# Schematic.net
KiCad netlist of a schematic drawn in EAGLE
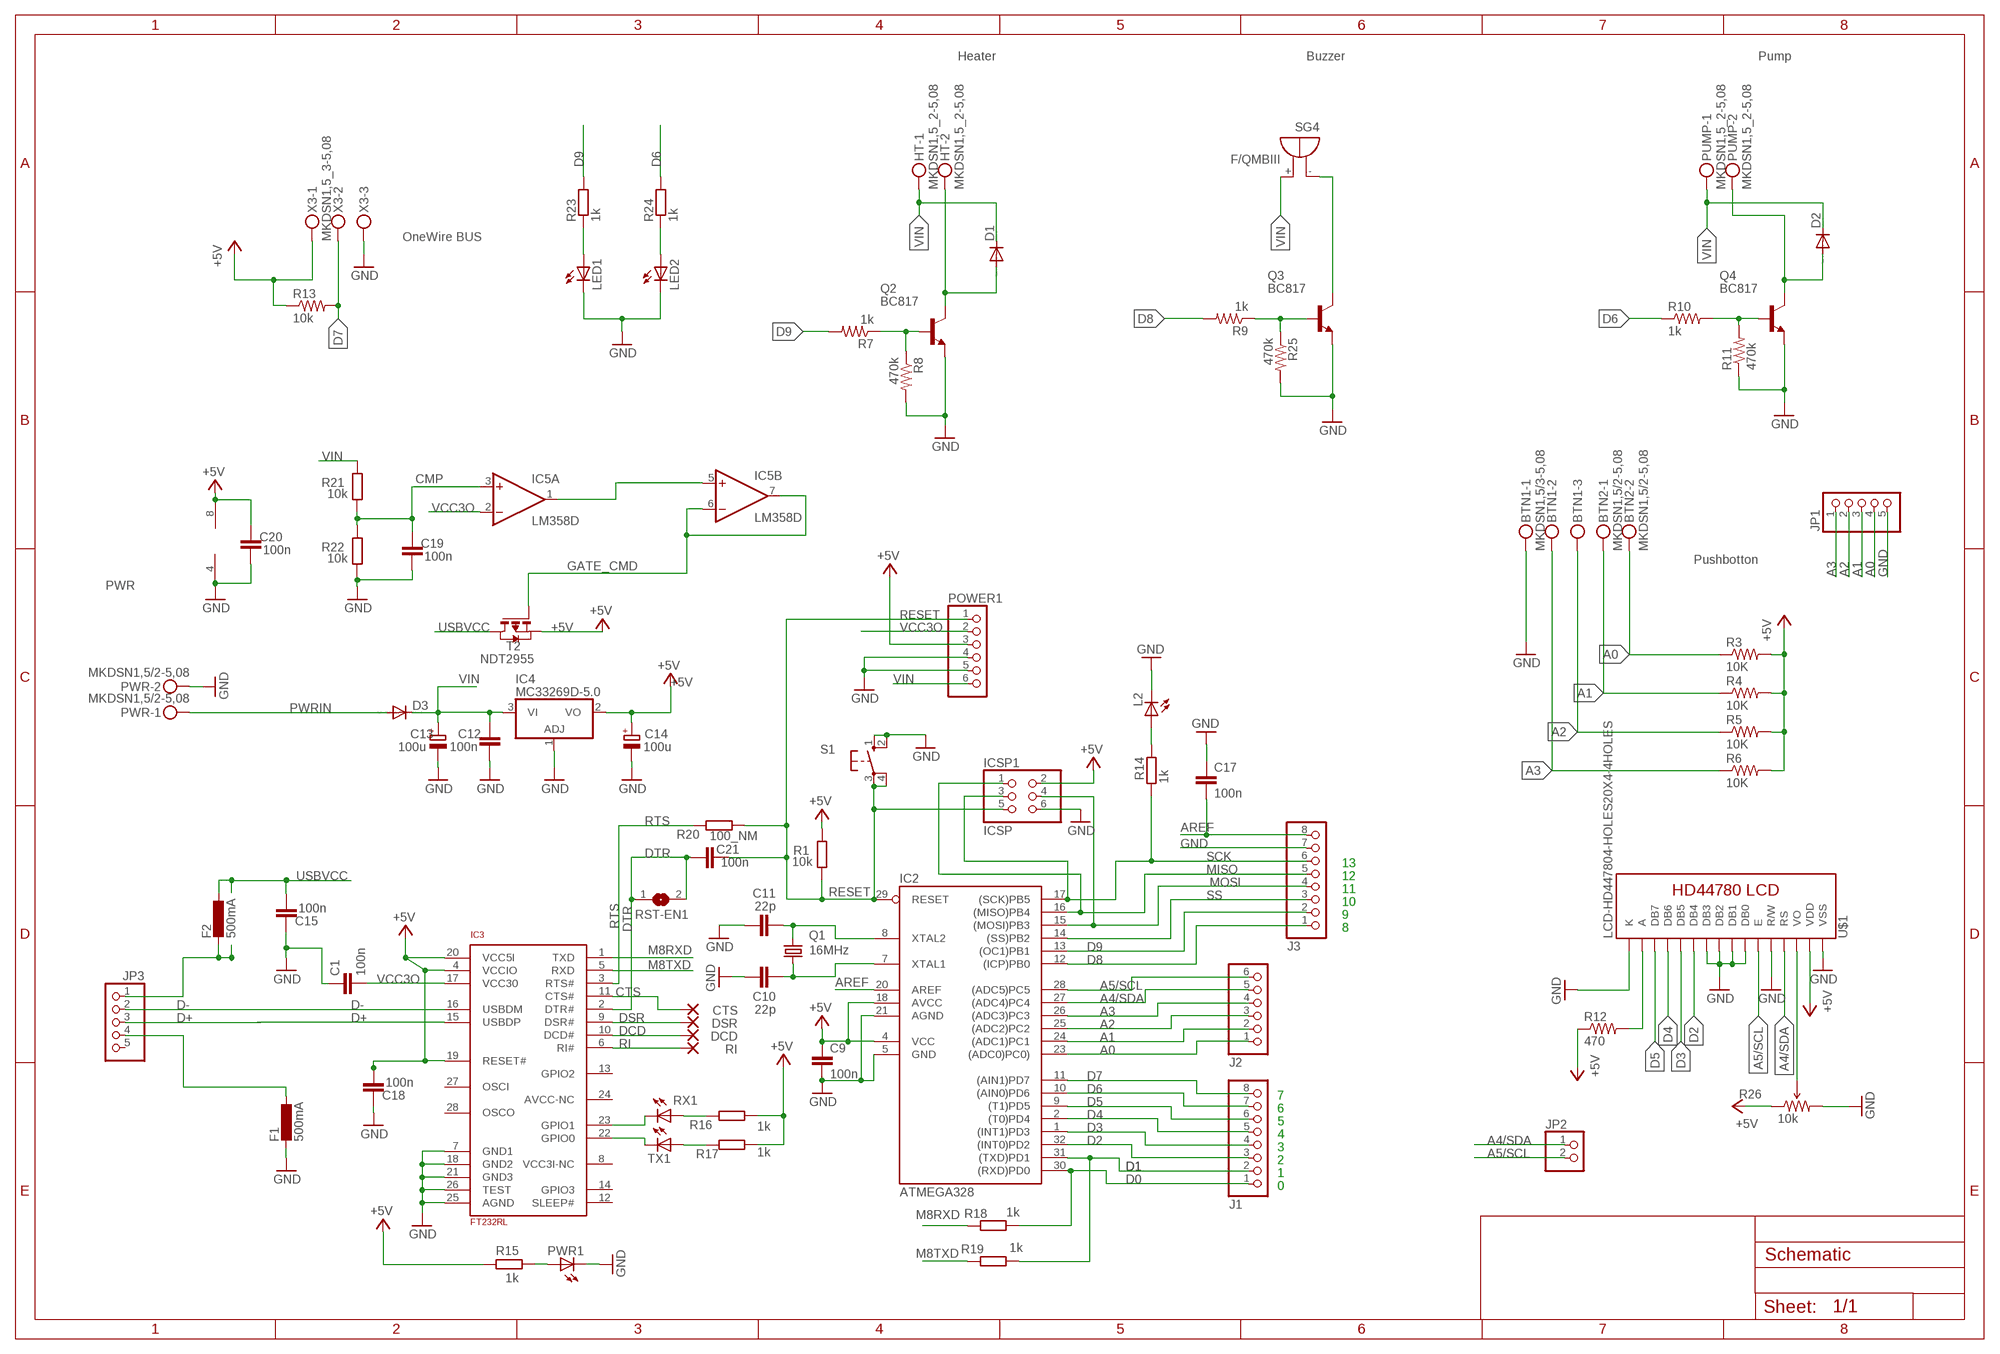
[diagram p0: schematic, sheet 1]

(export (version "E")
  (design (tool "Eeschema 10.0.6"))
  (components
    (comp (ref "BTN1")
      (value "MKDSN1,5/3-5,08")
      (footprint "eagle-import:MKDSN1,5_3-5,08")
      (fields (field (name "OC_NEWARK") "unknown"))
      (libsource (lib "eagle-import") (part "MKDSN1,5/3-5,08"))
    )
    (comp (ref "BTN2")
      (value "MKDSN1,5/2-5,08")
      (footprint "eagle-import:MKDSN1,5_2-5,08")
      (fields (field (name "OC_NEWARK") "unknown"))
      (libsource (lib "eagle-import") (part "MKDSN1,5/2-5,08"))
    )
    (comp (ref "C1")
      (value "100n")
      (footprint "eagle-import:C0603")
      (libsource (lib "eagle-import") (part "C-EUC0603"))
    )
    (comp (ref "C9")
      (value "100n")
      (footprint "eagle-import:C0603")
      (libsource (lib "eagle-import") (part "C-EUC0603"))
    )
    (comp (ref "C10")
      (value "22p")
      (footprint "eagle-import:C0603")
      (libsource (lib "eagle-import") (part "C-EUC0603"))
    )
    (comp (ref "C11")
      (value "22p")
      (footprint "eagle-import:C0603")
      (libsource (lib "eagle-import") (part "C-EUC0603"))
    )
    (comp (ref "C12")
      (value "100n")
      (footprint "eagle-import:C0603")
      (libsource (lib "eagle-import") (part "C-EUC0603"))
    )
    (comp (ref "C13")
      (value "100u")
      (footprint "eagle-import:PANASONIC_D")
      (libsource (lib "eagle-import") (part "CPOL-EUD"))
    )
    (comp (ref "C14")
      (value "100u")
      (footprint "eagle-import:PANASONIC_D")
      (libsource (lib "eagle-import") (part "CPOL-EUD"))
    )
    (comp (ref "C15")
      (value "100n")
      (footprint "eagle-import:C0603")
      (libsource (lib "eagle-import") (part "C-EUC0603"))
    )
    (comp (ref "C17")
      (value "100n")
      (footprint "eagle-import:C0603")
      (libsource (lib "eagle-import") (part "C-EUC0603"))
    )
    (comp (ref "C18")
      (value "100n")
      (footprint "eagle-import:C0603")
      (libsource (lib "eagle-import") (part "C-EUC0603"))
    )
    (comp (ref "C19")
      (value "100n")
      (footprint "eagle-import:C0603")
      (libsource (lib "eagle-import") (part "C-EUC0603"))
    )
    (comp (ref "C20")
      (value "100n")
      (footprint "eagle-import:C0603")
      (libsource (lib "eagle-import") (part "C-EUC0603"))
    )
    (comp (ref "C21")
      (value "100n")
      (footprint "eagle-import:C0603")
      (libsource (lib "eagle-import") (part "C-EUC0603"))
    )
    (comp (ref "CTS")
      (value "SMD2")
      (footprint "eagle-import:SMD1,27-2,54")
      (libsource (lib "eagle-import") (part "SMD2"))
    )
    (comp (ref "D1")
      (value "DIODE-SMB")
      (footprint "eagle-import:SMB")
      (libsource (lib "eagle-import") (part "DIODE-SMB"))
    )
    (comp (ref "D2")
      (value "DIODE-SMB")
      (footprint "eagle-import:SMB")
      (libsource (lib "eagle-import") (part "DIODE-SMB"))
    )
    (comp (ref "D3")
      (value "DIODE-SMB")
      (footprint "eagle-import:SMB")
      (libsource (lib "eagle-import") (part "DIODE-SMB"))
    )
    (comp (ref "DCD")
      (value "SMD2")
      (footprint "eagle-import:SMD1,27-2,54")
      (libsource (lib "eagle-import") (part "SMD2"))
    )
    (comp (ref "DSR")
      (value "SMD2")
      (footprint "eagle-import:SMD1,27-2,54")
      (libsource (lib "eagle-import") (part "SMD2"))
    )
    (comp (ref "F1")
      (value "500mA")
      (footprint "eagle-import:L1812")
      (libsource (lib "eagle-import") (part "L-EUL1812"))
    )
    (comp (ref "F2")
      (value "500mA")
      (footprint "eagle-import:L1812")
      (libsource (lib "eagle-import") (part "L-EUL1812"))
    )
    (comp (ref "HT")
      (value "MKDSN1,5_2-5,08")
      (footprint "eagle-import:MKDSN1,5-2-5,08")
      (fields (field (name "OC_NEWARK") "unknown"))
      (libsource (lib "eagle-import") (part "MKDSN1,5_2-5,08"))
    )
    (comp (ref "IC2")
      (value "ATMEGA328")
      (footprint "eagle-import:TQFP32-08")
      (libsource (lib "eagle-import") (part "AT90S4433A"))
    )
    (comp (ref "IC3")
      (value "FT232RL")
      (footprint "eagle-import:SSOP28")
      (libsource (lib "eagle-import") (part "FT232RL"))
    )
    (comp (ref "IC4")
      (value "MC33269D-5.0")
      (footprint "eagle-import:DPACK")
      (libsource (lib "eagle-import") (part "MC33269?D-5.0"))
    )
    (comp (ref "IC5")
      (value "LM358D")
      (footprint "eagle-import:SO08")
      (libsource (lib "eagle-import") (part "LM358D"))
    )
    (comp (ref "ICSP1")
      (value "ICSP")
      (footprint "eagle-import:2X03")
      (libsource (lib "eagle-import") (part "PINHD-2X3"))
    )
    (comp (ref "J1")
      (value "PINHD-1X8")
      (footprint "eagle-import:1X08")
      (libsource (lib "eagle-import") (part "PINHD-1X8"))
    )
    (comp (ref "J2")
      (value "PINHD-1X6")
      (footprint "eagle-import:1X06")
      (libsource (lib "eagle-import") (part "PINHD-1X6"))
    )
    (comp (ref "J3")
      (value "PINHD-1X8")
      (footprint "eagle-import:1X08")
      (libsource (lib "eagle-import") (part "PINHD-1X8"))
    )
    (comp (ref "JP1")
      (value "PINHD-1X5/90")
      (footprint "eagle-import:1X05_90")
      (libsource (lib "eagle-import") (part "PINHD-1X5/90"))
    )
    (comp (ref "JP2")
      (value "PINHD-1X2/90")
      (footprint "eagle-import:1X02_90")
      (libsource (lib "eagle-import") (part "PINHD-1X2/90"))
    )
    (comp (ref "JP3")
      (value "PINHD-1X5/90")
      (footprint "eagle-import:1X05_90")
      (libsource (lib "eagle-import") (part "PINHD-1X5/90"))
    )
    (comp (ref "L2")
      (value "LEDSML0805")
      (footprint "eagle-import:SML0805")
      (libsource (lib "eagle-import") (part "LEDSML0805"))
    )
    (comp (ref "LED1")
      (value "LED5MM")
      (footprint "eagle-import:LED5MM")
      (libsource (lib "eagle-import") (part "LED5MM"))
    )
    (comp (ref "LED2")
      (value "LED5MM")
      (footprint "eagle-import:LED5MM")
      (libsource (lib "eagle-import") (part "LED5MM"))
    )
    (comp (ref "POWER1")
      (value "PINHD-1X6")
      (footprint "eagle-import:1X06")
      (libsource (lib "eagle-import") (part "PINHD-1X6"))
    )
    (comp (ref "PUMP")
      (value "MKDSN1,5_2-5,08")
      (footprint "eagle-import:MKDSN1,5-2-5,08")
      (fields (field (name "OC_NEWARK") "unknown"))
      (libsource (lib "eagle-import") (part "MKDSN1,5_2-5,08"))
    )
    (comp (ref "PWR")
      (value "MKDSN1,5/2-5,08")
      (footprint "eagle-import:MKDSN1,5_2-5,08")
      (fields (field (name "OC_NEWARK") "unknown"))
      (libsource (lib "eagle-import") (part "MKDSN1,5/2-5,08"))
    )
    (comp (ref "PWR1")
      (value "LEDSML0805")
      (footprint "eagle-import:SML0805")
      (libsource (lib "eagle-import") (part "LEDSML0805"))
    )
    (comp (ref "Q1")
      (value "16MHz")
      (footprint "eagle-import:HC49_S")
      (libsource (lib "eagle-import") (part "CRYTALHC49S"))
    )
    (comp (ref "Q2")
      (value "BC817")
      (footprint "eagle-import:SOT23-BEC")
      (libsource (lib "eagle-import") (part "-NPN-SOT23-BECBC817"))
    )
    (comp (ref "Q3")
      (value "BC817")
      (footprint "eagle-import:SOT23-BEC")
      (libsource (lib "eagle-import") (part "-NPN-SOT23-BECBC817"))
    )
    (comp (ref "Q4")
      (value "BC817")
      (footprint "eagle-import:SOT23-BEC")
      (libsource (lib "eagle-import") (part "-NPN-SOT23-BECBC817"))
    )
    (comp (ref "R1")
      (value "10k")
      (footprint "eagle-import:R0603")
      (libsource (lib "eagle-import") (part "R-EU_R0603"))
    )
    (comp (ref "R3")
      (value "10K")
      (footprint "eagle-import:R0603")
      (libsource (lib "eagle-import") (part "R-US_R0603"))
    )
    (comp (ref "R4")
      (value "10K")
      (footprint "eagle-import:R0603")
      (libsource (lib "eagle-import") (part "R-US_R0603"))
    )
    (comp (ref "R5")
      (value "10K")
      (footprint "eagle-import:R0603")
      (libsource (lib "eagle-import") (part "R-US_R0603"))
    )
    (comp (ref "R6")
      (value "10K")
      (footprint "eagle-import:R0603")
      (libsource (lib "eagle-import") (part "R-US_R0603"))
    )
    (comp (ref "R7")
      (value "1k")
      (footprint "eagle-import:R0603")
      (libsource (lib "eagle-import") (part "R-US_R0603"))
    )
    (comp (ref "R8")
      (value "470k")
      (footprint "eagle-import:R0603")
      (libsource (lib "eagle-import") (part "R-US_R0603"))
    )
    (comp (ref "R9")
      (value "1k")
      (footprint "eagle-import:R0603")
      (libsource (lib "eagle-import") (part "R-US_R0603"))
    )
    (comp (ref "R10")
      (value "1k")
      (footprint "eagle-import:R0603")
      (libsource (lib "eagle-import") (part "R-US_R0603"))
    )
    (comp (ref "R11")
      (value "470k")
      (footprint "eagle-import:R0603")
      (libsource (lib "eagle-import") (part "R-US_R0603"))
    )
    (comp (ref "R12")
      (value "470")
      (footprint "eagle-import:R1206")
      (libsource (lib "eagle-import") (part "R-US_R1206"))
    )
    (comp (ref "R13")
      (value "10k")
      (footprint "eagle-import:R0603")
      (libsource (lib "eagle-import") (part "R-US_R0603"))
    )
    (comp (ref "R14")
      (value "1k")
      (footprint "eagle-import:R0603")
      (libsource (lib "eagle-import") (part "R-EU_R0603"))
    )
    (comp (ref "R15")
      (value "1k")
      (footprint "eagle-import:R0603")
      (libsource (lib "eagle-import") (part "R-EU_R0603"))
    )
    (comp (ref "R16")
      (value "1k")
      (footprint "eagle-import:R0603")
      (libsource (lib "eagle-import") (part "R-EU_R0603"))
    )
    (comp (ref "R17")
      (value "1k")
      (footprint "eagle-import:R0603")
      (libsource (lib "eagle-import") (part "R-EU_R0603"))
    )
    (comp (ref "R18")
      (value "1k")
      (footprint "eagle-import:R0603")
      (libsource (lib "eagle-import") (part "R-EU_R0603"))
    )
    (comp (ref "R19")
      (value "1k")
      (footprint "eagle-import:R0603")
      (libsource (lib "eagle-import") (part "R-EU_R0603"))
    )
    (comp (ref "R20")
      (value "100_NM")
      (footprint "eagle-import:R0603")
      (libsource (lib "eagle-import") (part "R-EU_R0603"))
    )
    (comp (ref "R21")
      (value "10k")
      (footprint "eagle-import:R0603")
      (libsource (lib "eagle-import") (part "R-EU_R0603"))
    )
    (comp (ref "R22")
      (value "10k")
      (footprint "eagle-import:R0603")
      (libsource (lib "eagle-import") (part "R-EU_R0603"))
    )
    (comp (ref "R23")
      (value "1k")
      (footprint "eagle-import:R0603")
      (libsource (lib "eagle-import") (part "R-EU_R0603"))
    )
    (comp (ref "R24")
      (value "1k")
      (footprint "eagle-import:R0603")
      (libsource (lib "eagle-import") (part "R-EU_R0603"))
    )
    (comp (ref "R25")
      (value "470k")
      (footprint "eagle-import:R0603")
      (libsource (lib "eagle-import") (part "R-US_R0603"))
    )
    (comp (ref "R26")
      (value "10k")
      (footprint "eagle-import:TRIMPOT-5MM")
      (libsource (lib "eagle-import") (part "TRIMPOTTRIMPOT-5MM"))
    )
    (comp (ref "RI")
      (value "SMD2")
      (footprint "eagle-import:SMD1,27-2,54")
      (libsource (lib "eagle-import") (part "SMD2"))
    )
    (comp (ref "RST-EN1")
      (value "SJ")
      (footprint "eagle-import:SJ")
      (libsource (lib "eagle-import") (part "SJ"))
    )
    (comp (ref "RX1")
      (value "LEDSML0805")
      (footprint "eagle-import:SML0805")
      (libsource (lib "eagle-import") (part "LEDSML0805"))
    )
    (comp (ref "S1")
      (value "10-XX")
      (footprint "eagle-import:B3F-10XX")
      (fields (field (name "MPN") "B3F-1000"))
      (libsource (lib "eagle-import") (part "10-XX"))
    )
    (comp (ref "SG4")
      (value "F/QMBIII")
      (footprint "eagle-import:F_QMBIII")
      (libsource (lib "eagle-import") (part "F/QMBIII"))
    )
    (comp (ref "T2")
      (value "NDT2955")
      (footprint "eagle-import:SOT223")
      (libsource (lib "eagle-import") (part "PMOSSOT223"))
    )
    (comp (ref "TX1")
      (value "LEDSML0805")
      (footprint "eagle-import:SML0805")
      (libsource (lib "eagle-import") (part "LEDSML0805"))
    )
    (comp (ref "U$1")
      (value "LCD-HD447804-HOLES20X4-4HOLES")
      (footprint "eagle-import:LCD-20X4-4HOLES")
      (libsource (lib "eagle-import") (part "LCD-HD4478020X4-4HOLES4-HOLES"))
    )
    (comp (ref "X3")
      (value "MKDSN1,5_3-5,08")
      (footprint "eagle-import:MKDSN1,5-3-5,08")
      (fields (field (name "OC_NEWARK") "unknown"))
      (libsource (lib "eagle-import") (part "MKDSN1,5_3-5,08"))
    )
  )
  (nets
    (net (code "1") (name "+5V") (class "Default")
      (node (ref "C14") (pin "+") (pinfunction "+_+") (pintype "passive"))
      (node (ref "C18") (pin "1") (pinfunction "1_1") (pintype "passive"))
      (node (ref "C20") (pin "2") (pinfunction "2_2") (pintype "passive"))
      (node (ref "C9") (pin "1") (pinfunction "1_1") (pintype "passive"))
      (node (ref "IC2") (pin "18") (pinfunction "AVCC_18") (pintype "power_in"))
      (node (ref "IC2") (pin "4") (pinfunction "VCC_4") (pintype "power_in"))
      (node (ref "IC3") (pin "19") (pinfunction "RESET#_19") (pintype "input"))
      (node (ref "IC3") (pin "20") (pinfunction "VCC5I_20") (pintype "power_in"))
      (node (ref "IC3") (pin "4") (pinfunction "VCCIO_4") (pintype "power_in"))
      (node (ref "IC4") (pin "2") (pinfunction "VO_2") (pintype "passive"))
      (node (ref "IC5") (pin "8") (pinfunction "V+_8") (pintype "power_in"))
      (node (ref "ICSP1") (pin "2") (pinfunction "2_2") (pintype "passive"))
      (node (ref "POWER1") (pin "3") (pinfunction "3_3") (pintype "passive"))
      (node (ref "R1") (pin "2") (pinfunction "2_2") (pintype "passive"))
      (node (ref "R12") (pin "1") (pinfunction "1_1") (pintype "passive"))
      (node (ref "R13") (pin "1") (pinfunction "1_1") (pintype "passive"))
      (node (ref "R15") (pin "1") (pinfunction "1_1") (pintype "passive"))
      (node (ref "R16") (pin "2") (pinfunction "2_2") (pintype "passive"))
      (node (ref "R17") (pin "2") (pinfunction "2_2") (pintype "passive"))
      (node (ref "R26") (pin "A") (pinfunction "CCW_A") (pintype "passive"))
      (node (ref "R3") (pin "2") (pinfunction "2_2") (pintype "passive"))
      (node (ref "R4") (pin "2") (pinfunction "2_2") (pintype "passive"))
      (node (ref "R5") (pin "2") (pinfunction "2_2") (pintype "passive"))
      (node (ref "R6") (pin "2") (pinfunction "2_2") (pintype "passive"))
      (node (ref "T2") (pin "3") (pinfunction "S_3") (pintype "passive"))
      (node (ref "U$1") (pin "P$2") (pinfunction "VDD_P$2") (pintype "power_in"))
      (node (ref "X3") (pin "1") (pinfunction "KL_1") (pintype "passive"))
    )
    (net (code "2") (name "/AREF") (class "Default")
      (node (ref "C17") (pin "2") (pinfunction "2_2") (pintype "passive"))
      (node (ref "IC2") (pin "20") (pinfunction "AREF_20") (pintype "passive"))
      (node (ref "J3") (pin "8") (pinfunction "8_8") (pintype "passive"))
    )
    (net (code "3") (name "/CMP") (class "Default")
      (node (ref "C19") (pin "2") (pinfunction "2_2") (pintype "passive"))
      (node (ref "IC5") (pin "3") (pinfunction "+IN_3") (pintype "input"))
      (node (ref "R21") (pin "1") (pinfunction "1_1") (pintype "passive"))
      (node (ref "R22") (pin "2") (pinfunction "2_2") (pintype "passive"))
    )
    (net (code "4") (name "/CTS") (class "Default")
      (node (ref "CTS") (pin "1") (pinfunction "P_1") (pintype "passive"))
      (node (ref "IC3") (pin "11") (pinfunction "CTS#_11") (pintype "input"))
    )
    (net (code "5") (name "/D+") (class "Default")
      (node (ref "IC3") (pin "15") (pinfunction "USBDP_15") (pintype "bidirectional"))
      (node (ref "JP3") (pin "3") (pinfunction "3_3") (pintype "passive"))
    )
    (net (code "6") (name "/D-") (class "Default")
      (node (ref "IC3") (pin "16") (pinfunction "USBDM_16") (pintype "bidirectional"))
      (node (ref "JP3") (pin "2") (pinfunction "2_2") (pintype "passive"))
    )
    (net (code "7") (name "/D0") (class "Default")
      (node (ref "IC2") (pin "30") (pinfunction "(RXD)PD0_30") (pintype "bidirectional"))
      (node (ref "J1") (pin "1") (pinfunction "1_1") (pintype "passive"))
      (node (ref "R18") (pin "1") (pinfunction "1_1") (pintype "passive"))
    )
    (net (code "8") (name "/D1") (class "Default")
      (node (ref "IC2") (pin "31") (pinfunction "(TXD)PD1_31") (pintype "bidirectional"))
      (node (ref "J1") (pin "2") (pinfunction "2_2") (pintype "passive"))
      (node (ref "R19") (pin "1") (pinfunction "1_1") (pintype "passive"))
    )
    (net (code "9") (name "/DCD") (class "Default")
      (node (ref "DCD") (pin "1") (pinfunction "P_1") (pintype "passive"))
      (node (ref "IC3") (pin "10") (pinfunction "DCD#_10") (pintype "input"))
    )
    (net (code "10") (name "/DSR") (class "Default")
      (node (ref "DSR") (pin "1") (pinfunction "P_1") (pintype "passive"))
      (node (ref "IC3") (pin "9") (pinfunction "DSR#_9") (pintype "input"))
    )
    (net (code "11") (name "/DTR") (class "Default")
      (node (ref "C21") (pin "1") (pinfunction "1_1") (pintype "passive"))
      (node (ref "IC3") (pin "2") (pinfunction "DTR#_2") (pintype "output"))
      (node (ref "RST-EN1") (pin "1") (pinfunction "1_1") (pintype "passive"))
      (node (ref "RST-EN1") (pin "2") (pinfunction "2_2") (pintype "passive"))
    )
    (net (code "12") (name "/GATE_CMD") (class "Default")
      (node (ref "IC5") (pin "6") (pinfunction "-IN_6") (pintype "input"))
      (node (ref "IC5") (pin "7") (pinfunction "OUT_7") (pintype "output"))
      (node (ref "T2") (pin "1") (pinfunction "G_1") (pintype "passive"))
    )
    (net (code "13") (name "/M8RXD") (class "Default")
      (node (ref "IC3") (pin "1") (pinfunction "TXD_1") (pintype "output"))
      (node (ref "R18") (pin "2") (pinfunction "2_2") (pintype "passive"))
    )
    (net (code "14") (name "/M8TXD") (class "Default")
      (node (ref "IC3") (pin "5") (pinfunction "RXD_5") (pintype "input"))
      (node (ref "R19") (pin "2") (pinfunction "2_2") (pintype "passive"))
    )
    (net (code "15") (name "/MISO") (class "Default")
      (node (ref "IC2") (pin "16") (pinfunction "(MISO)PB4_16") (pintype "bidirectional"))
      (node (ref "ICSP1") (pin "1") (pinfunction "1_1") (pintype "passive"))
      (node (ref "J3") (pin "5") (pinfunction "5_5") (pintype "passive"))
    )
    (net (code "16") (name "/MOSI") (class "Default")
      (node (ref "IC2") (pin "15") (pinfunction "(MOSI)PB3_15") (pintype "bidirectional"))
      (node (ref "ICSP1") (pin "4") (pinfunction "4_4") (pintype "passive"))
      (node (ref "J3") (pin "4") (pinfunction "4_4") (pintype "passive"))
    )
    (net (code "17") (name "/PWRIN") (class "Default")
      (node (ref "D3") (pin "A") (pinfunction "A_A") (pintype "passive"))
      (node (ref "PWR") (pin "1") (pinfunction "KL_1") (pintype "passive"))
    )
    (net (code "18") (name "/RESET") (class "Default")
      (node (ref "C21") (pin "2") (pinfunction "2_2") (pintype "passive"))
      (node (ref "IC2") (pin "29") (pinfunction "RESET_29") (pintype "input"))
      (node (ref "ICSP1") (pin "5") (pinfunction "5_5") (pintype "passive"))
      (node (ref "POWER1") (pin "1") (pinfunction "1_1") (pintype "passive"))
      (node (ref "R1") (pin "1") (pinfunction "1_1") (pintype "passive"))
      (node (ref "R20") (pin "2") (pinfunction "2_2") (pintype "passive"))
      (node (ref "S1") (pin "3") (pinfunction "P_3") (pintype "passive"))
      (node (ref "S1") (pin "4") (pinfunction "P1_4") (pintype "passive"))
    )
    (net (code "19") (name "/RI") (class "Default")
      (node (ref "IC3") (pin "6") (pinfunction "RI#_6") (pintype "input"))
      (node (ref "RI") (pin "1") (pinfunction "P_1") (pintype "passive"))
    )
    (net (code "20") (name "/RTS") (class "Default")
      (node (ref "IC3") (pin "3") (pinfunction "RTS#_3") (pintype "output"))
      (node (ref "R20") (pin "1") (pinfunction "1_1") (pintype "passive"))
    )
    (net (code "21") (name "/SCK") (class "Default")
      (node (ref "IC2") (pin "17") (pinfunction "(SCK)PB5_17") (pintype "bidirectional"))
      (node (ref "ICSP1") (pin "3") (pinfunction "3_3") (pintype "passive"))
      (node (ref "J3") (pin "6") (pinfunction "6_6") (pintype "passive"))
      (node (ref "R14") (pin "2") (pinfunction "2_2") (pintype "passive"))
    )
    (net (code "22") (name "/SS") (class "Default")
      (node (ref "IC2") (pin "14") (pinfunction "(SS)PB2_14") (pintype "bidirectional"))
      (node (ref "J3") (pin "3") (pinfunction "3_3") (pintype "passive"))
    )
    (net (code "23") (name "/USBVCC") (class "Default")
      (node (ref "C15") (pin "1") (pinfunction "1_1") (pintype "passive"))
      (node (ref "F2") (pin "1") (pinfunction "1_1") (pintype "passive"))
      (node (ref "T2") (pin "2") (pinfunction "D_2") (pintype "passive"))
      (node (ref "T2") (pin "4") (pinfunction "D_4") (pintype "passive"))
    )
    (net (code "24") (name "/VCC3O") (class "Default")
      (node (ref "C1") (pin "2") (pinfunction "2_2") (pintype "passive"))
      (node (ref "IC3") (pin "17") (pinfunction "VCC30_17") (pintype "power_in"))
      (node (ref "IC5") (pin "2") (pinfunction "-IN_2") (pintype "input"))
      (node (ref "POWER1") (pin "2") (pinfunction "2_2") (pintype "passive"))
    )
    (net (code "25") (name "A0") (class "Default")
      (node (ref "BTN2") (pin "2") (pinfunction "KL_2") (pintype "passive"))
      (node (ref "IC2") (pin "23") (pinfunction "(ADC0)PC0)_23") (pintype "bidirectional"))
      (node (ref "J2") (pin "1") (pinfunction "1_1") (pintype "passive"))
      (node (ref "JP1") (pin "4") (pinfunction "4_4") (pintype "passive"))
      (node (ref "R3") (pin "1") (pinfunction "1_1") (pintype "passive"))
    )
    (net (code "26") (name "A1") (class "Default")
      (node (ref "BTN2") (pin "1") (pinfunction "KL_1") (pintype "passive"))
      (node (ref "IC2") (pin "24") (pinfunction "(ADC1)PC1_24") (pintype "bidirectional"))
      (node (ref "J2") (pin "2") (pinfunction "2_2") (pintype "passive"))
      (node (ref "JP1") (pin "3") (pinfunction "3_3") (pintype "passive"))
      (node (ref "R4") (pin "1") (pinfunction "1_1") (pintype "passive"))
    )
    (net (code "27") (name "A2") (class "Default")
      (node (ref "BTN1") (pin "3") (pinfunction "KL_3") (pintype "passive"))
      (node (ref "IC2") (pin "25") (pinfunction "(ADC2)PC2_25") (pintype "bidirectional"))
      (node (ref "J2") (pin "3") (pinfunction "3_3") (pintype "passive"))
      (node (ref "JP1") (pin "2") (pinfunction "2_2") (pintype "passive"))
      (node (ref "R5") (pin "1") (pinfunction "1_1") (pintype "passive"))
    )
    (net (code "28") (name "A3") (class "Default")
      (node (ref "BTN1") (pin "2") (pinfunction "KL_2") (pintype "passive"))
      (node (ref "IC2") (pin "26") (pinfunction "(ADC3)PC3_26") (pintype "bidirectional"))
      (node (ref "J2") (pin "4") (pinfunction "4_4") (pintype "passive"))
      (node (ref "JP1") (pin "1") (pinfunction "1_1") (pintype "passive"))
      (node (ref "R6") (pin "1") (pinfunction "1_1") (pintype "passive"))
    )
    (net (code "29") (name "A4{slash}SDA") (class "Default")
      (node (ref "IC2") (pin "27") (pinfunction "(ADC4)PC4_27") (pintype "bidirectional"))
      (node (ref "J2") (pin "5") (pinfunction "5_5") (pintype "passive"))
      (node (ref "JP2") (pin "1") (pinfunction "1_1") (pintype "passive"))
      (node (ref "U$1") (pin "P$4") (pinfunction "RS_P$4") (pintype "input"))
    )
    (net (code "30") (name "A5{slash}SCL") (class "Default")
      (node (ref "IC2") (pin "28") (pinfunction "(ADC5)PC5_28") (pintype "bidirectional"))
      (node (ref "J2") (pin "6") (pinfunction "6_6") (pintype "passive"))
      (node (ref "JP2") (pin "2") (pinfunction "2_2") (pintype "passive"))
      (node (ref "U$1") (pin "P$6") (pinfunction "E_P$6") (pintype "input"))
    )
    (net (code "31") (name "D2") (class "Default")
      (node (ref "IC2") (pin "32") (pinfunction "(INT0)PD2_32") (pintype "bidirectional"))
      (node (ref "J1") (pin "3") (pinfunction "3_3") (pintype "passive"))
      (node (ref "U$1") (pin "P$11") (pinfunction "DB4_P$11") (pintype "bidirectional"))
    )
    (net (code "32") (name "D3") (class "Default")
      (node (ref "IC2") (pin "1") (pinfunction "(INT1)PD3_1") (pintype "bidirectional"))
      (node (ref "J1") (pin "4") (pinfunction "4_4") (pintype "passive"))
      (node (ref "U$1") (pin "P$12") (pinfunction "DB5_P$12") (pintype "bidirectional"))
    )
    (net (code "33") (name "D4") (class "Default")
      (node (ref "IC2") (pin "2") (pinfunction "(T0)PD4_2") (pintype "bidirectional"))
      (node (ref "J1") (pin "5") (pinfunction "5_5") (pintype "passive"))
      (node (ref "U$1") (pin "P$13") (pinfunction "DB6_P$13") (pintype "bidirectional"))
    )
    (net (code "34") (name "D5") (class "Default")
      (node (ref "IC2") (pin "9") (pinfunction "(T1)PD5_9") (pintype "bidirectional"))
      (node (ref "J1") (pin "6") (pinfunction "6_6") (pintype "passive"))
      (node (ref "U$1") (pin "P$14") (pinfunction "DB7_P$14") (pintype "bidirectional"))
    )
    (net (code "35") (name "D6") (class "Default")
      (node (ref "IC2") (pin "10") (pinfunction "(AIN0)PD6_10") (pintype "bidirectional"))
      (node (ref "J1") (pin "7") (pinfunction "7_7") (pintype "passive"))
      (node (ref "R10") (pin "1") (pinfunction "1_1") (pintype "passive"))
      (node (ref "R24") (pin "2") (pinfunction "2_2") (pintype "passive"))
    )
    (net (code "36") (name "D7") (class "Default")
      (node (ref "IC2") (pin "11") (pinfunction "(AIN1)PD7_11") (pintype "bidirectional"))
      (node (ref "J1") (pin "8") (pinfunction "8_8") (pintype "passive"))
      (node (ref "R13") (pin "2") (pinfunction "2_2") (pintype "passive"))
      (node (ref "X3") (pin "2") (pinfunction "KL_2") (pintype "passive"))
    )
    (net (code "37") (name "D8") (class "Default")
      (node (ref "IC2") (pin "12") (pinfunction "(ICP)PB0_12") (pintype "bidirectional"))
      (node (ref "J3") (pin "1") (pinfunction "1_1") (pintype "passive"))
      (node (ref "R9") (pin "2") (pinfunction "2_2") (pintype "passive"))
    )
    (net (code "38") (name "D9") (class "Default")
      (node (ref "IC2") (pin "13") (pinfunction "(OC1)PB1_13") (pintype "bidirectional"))
      (node (ref "J3") (pin "2") (pinfunction "2_2") (pintype "passive"))
      (node (ref "R23") (pin "2") (pinfunction "2_2") (pintype "passive"))
      (node (ref "R7") (pin "2") (pinfunction "2_2") (pintype "passive"))
    )
    (net (code "39") (name "GND") (class "Default")
      (node (ref "BTN1") (pin "1") (pinfunction "KL_1") (pintype "passive"))
      (node (ref "C1") (pin "1") (pinfunction "1_1") (pintype "passive"))
      (node (ref "C10") (pin "1") (pinfunction "1_1") (pintype "passive"))
      (node (ref "C11") (pin "1") (pinfunction "1_1") (pintype "passive"))
      (node (ref "C12") (pin "1") (pinfunction "1_1") (pintype "passive"))
      (node (ref "C13") (pin "-") (pinfunction "-_-") (pintype "passive"))
      (node (ref "C14") (pin "-") (pinfunction "-_-") (pintype "passive"))
      (node (ref "C15") (pin "2") (pinfunction "2_2") (pintype "passive"))
      (node (ref "C17") (pin "1") (pinfunction "1_1") (pintype "passive"))
      (node (ref "C18") (pin "2") (pinfunction "2_2") (pintype "passive"))
      (node (ref "C19") (pin "1") (pinfunction "1_1") (pintype "passive"))
      (node (ref "C20") (pin "1") (pinfunction "1_1") (pintype "passive"))
      (node (ref "C9") (pin "2") (pinfunction "2_2") (pintype "passive"))
      (node (ref "F1") (pin "2") (pinfunction "2_2") (pintype "passive"))
      (node (ref "IC2") (pin "21") (pinfunction "AGND_21") (pintype "power_in"))
      (node (ref "IC2") (pin "5") (pinfunction "GND_5") (pintype "power_in"))
      (node (ref "IC3") (pin "18") (pinfunction "GND2_18") (pintype "power_in"))
      (node (ref "IC3") (pin "21") (pinfunction "GND3_21") (pintype "power_in"))
      (node (ref "IC3") (pin "25") (pinfunction "AGND_25") (pintype "power_in"))
      (node (ref "IC3") (pin "26") (pinfunction "TEST_26") (pintype "input"))
      (node (ref "IC3") (pin "7") (pinfunction "GND1_7") (pintype "power_in"))
      (node (ref "IC4") (pin "1") (pinfunction "ADJ_1") (pintype "input"))
      (node (ref "IC5") (pin "4") (pinfunction "V-_4") (pintype "power_in"))
      (node (ref "ICSP1") (pin "6") (pinfunction "6_6") (pintype "passive"))
      (node (ref "J3") (pin "7") (pinfunction "7_7") (pintype "passive"))
      (node (ref "JP1") (pin "5") (pinfunction "5_5") (pintype "passive"))
      (node (ref "L2") (pin "C") (pinfunction "C_C") (pintype "passive"))
      (node (ref "LED1") (pin "K") (pinfunction "C_K") (pintype "passive"))
      (node (ref "LED2") (pin "K") (pinfunction "C_K") (pintype "passive"))
      (node (ref "POWER1") (pin "4") (pinfunction "4_4") (pintype "passive"))
      (node (ref "POWER1") (pin "5") (pinfunction "5_5") (pintype "passive"))
      (node (ref "PWR") (pin "2") (pinfunction "KL_2") (pintype "passive"))
      (node (ref "PWR1") (pin "C") (pinfunction "C_C") (pintype "passive"))
      (node (ref "Q2") (pin "E") (pinfunction "E_E") (pintype "passive"))
      (node (ref "Q3") (pin "E") (pinfunction "E_E") (pintype "passive"))
      (node (ref "Q4") (pin "E") (pinfunction "E_E") (pintype "passive"))
      (node (ref "R11") (pin "1") (pinfunction "1_1") (pintype "passive"))
      (node (ref "R22") (pin "1") (pinfunction "1_1") (pintype "passive"))
      (node (ref "R25") (pin "2") (pinfunction "2_2") (pintype "passive"))
      (node (ref "R26") (pin "C") (pinfunction "CW_C") (pintype "passive"))
      (node (ref "R8") (pin "2") (pinfunction "2_2") (pintype "passive"))
      (node (ref "S1") (pin "1") (pinfunction "S_1") (pintype "passive"))
      (node (ref "S1") (pin "2") (pinfunction "S1_2") (pintype "passive"))
      (node (ref "U$1") (pin "P$1") (pinfunction "VSS_P$1") (pintype "power_in"))
      (node (ref "U$1") (pin "P$10") (pinfunction "DB3_P$10") (pintype "bidirectional"))
      (node (ref "U$1") (pin "P$16") (pinfunction "K_P$16") (pintype "power_in"))
      (node (ref "U$1") (pin "P$5") (pinfunction "R/W_P$5") (pintype "input"))
      (node (ref "U$1") (pin "P$7") (pinfunction "DB0_P$7") (pintype "bidirectional"))
      (node (ref "U$1") (pin "P$8") (pinfunction "DB1_P$8") (pintype "bidirectional"))
      (node (ref "U$1") (pin "P$9") (pinfunction "DB2_P$9") (pintype "bidirectional"))
      (node (ref "X3") (pin "3") (pinfunction "KL_3") (pintype "passive"))
    )
    (net (code "40") (name "Net-(F1-Pad1)") (class "Default")
      (node (ref "F1") (pin "1") (pinfunction "1_1") (pintype "passive"))
      (node (ref "JP3") (pin "4") (pinfunction "4_4") (pintype "passive"))
    )
    (net (code "41") (name "Net-(F2-Pad2)") (class "Default")
      (node (ref "F2") (pin "2") (pinfunction "2_2") (pintype "passive"))
      (node (ref "JP3") (pin "1") (pinfunction "1_1") (pintype "passive"))
    )
    (net (code "42") (name "Net-(HTB-KL)") (class "Default")
      (node (ref "D1") (pin "A") (pinfunction "A_A") (pintype "passive"))
      (node (ref "HT") (pin "2") (pinfunction "KL_2") (pintype "passive"))
      (node (ref "Q2") (pin "C") (pinfunction "C_C") (pintype "passive"))
    )
    (net (code "43") (name "Net-(IC2-XTAL1)") (class "Default")
      (node (ref "C10") (pin "2") (pinfunction "2_2") (pintype "passive"))
      (node (ref "IC2") (pin "7") (pinfunction "XTAL1_7") (pintype "bidirectional"))
      (node (ref "Q1") (pin "1") (pinfunction "1_1") (pintype "passive"))
    )
    (net (code "44") (name "Net-(IC2-XTAL2)") (class "Default")
      (node (ref "C11") (pin "2") (pinfunction "2_2") (pintype "passive"))
      (node (ref "IC2") (pin "8") (pinfunction "XTAL2_8") (pintype "bidirectional"))
      (node (ref "Q1") (pin "2") (pinfunction "2_2") (pintype "passive"))
    )
    (net (code "45") (name "Net-(IC3-GPIO0)") (class "Default")
      (node (ref "IC3") (pin "22") (pinfunction "GPIO0_22") (pintype "output"))
      (node (ref "TX1") (pin "C") (pinfunction "C_C") (pintype "passive"))
    )
    (net (code "46") (name "Net-(IC3-GPIO1)") (class "Default")
      (node (ref "IC3") (pin "23") (pinfunction "GPIO1_23") (pintype "output"))
      (node (ref "RX1") (pin "C") (pinfunction "C_C") (pintype "passive"))
    )
    (net (code "47") (name "Net-(IC5A-OUT)") (class "Default")
      (node (ref "IC5") (pin "1") (pinfunction "OUT_1") (pintype "output"))
      (node (ref "IC5") (pin "5") (pinfunction "+IN_5") (pintype "input"))
    )
    (net (code "48") (name "Net-(L2-PadA)") (class "Default")
      (node (ref "L2") (pin "A") (pinfunction "A_A") (pintype "passive"))
      (node (ref "R14") (pin "1") (pinfunction "1_1") (pintype "passive"))
    )
    (net (code "49") (name "Net-(LED1-PadA)") (class "Default")
      (node (ref "LED1") (pin "A") (pinfunction "A_A") (pintype "passive"))
      (node (ref "R23") (pin "1") (pinfunction "1_1") (pintype "passive"))
    )
    (net (code "50") (name "Net-(LED2-PadA)") (class "Default")
      (node (ref "LED2") (pin "A") (pinfunction "A_A") (pintype "passive"))
      (node (ref "R24") (pin "1") (pinfunction "1_1") (pintype "passive"))
    )
    (net (code "51") (name "Net-(PUMPB-KL)") (class "Default")
      (node (ref "D2") (pin "A") (pinfunction "A_A") (pintype "passive"))
      (node (ref "PUMP") (pin "2") (pinfunction "KL_2") (pintype "passive"))
      (node (ref "Q4") (pin "C") (pinfunction "C_C") (pintype "passive"))
    )
    (net (code "52") (name "Net-(PWR1-PadA)") (class "Default")
      (node (ref "PWR1") (pin "A") (pinfunction "A_A") (pintype "passive"))
      (node (ref "R15") (pin "2") (pinfunction "2_2") (pintype "passive"))
    )
    (net (code "53") (name "Net-(Q2-PadB)") (class "Default")
      (node (ref "Q2") (pin "B") (pinfunction "B_B") (pintype "passive"))
      (node (ref "R7") (pin "1") (pinfunction "1_1") (pintype "passive"))
      (node (ref "R8") (pin "1") (pinfunction "1_1") (pintype "passive"))
    )
    (net (code "54") (name "Net-(Q3-PadB)") (class "Default")
      (node (ref "Q3") (pin "B") (pinfunction "B_B") (pintype "passive"))
      (node (ref "R25") (pin "1") (pinfunction "1_1") (pintype "passive"))
      (node (ref "R9") (pin "1") (pinfunction "1_1") (pintype "passive"))
    )
    (net (code "55") (name "Net-(Q4-PadB)") (class "Default")
      (node (ref "Q4") (pin "B") (pinfunction "B_B") (pintype "passive"))
      (node (ref "R10") (pin "2") (pinfunction "2_2") (pintype "passive"))
      (node (ref "R11") (pin "2") (pinfunction "2_2") (pintype "passive"))
    )
    (net (code "56") (name "Net-(R16-Pad1)") (class "Default")
      (node (ref "R16") (pin "1") (pinfunction "1_1") (pintype "passive"))
      (node (ref "RX1") (pin "A") (pinfunction "A_A") (pintype "passive"))
    )
    (net (code "57") (name "Net-(R17-Pad1)") (class "Default")
      (node (ref "R17") (pin "1") (pinfunction "1_1") (pintype "passive"))
      (node (ref "TX1") (pin "A") (pinfunction "A_A") (pintype "passive"))
    )
    (net (code "58") (name "Net-(R26-WIPER)") (class "Default")
      (node (ref "R26") (pin "B") (pinfunction "WIPER_B") (pintype "passive"))
      (node (ref "U$1") (pin "P$3") (pinfunction "VO_P$3") (pintype "bidirectional"))
    )
    (net (code "59") (name "Net-(SG4-+)") (class "Default")
      (node (ref "Q3") (pin "C") (pinfunction "C_C") (pintype "passive"))
      (node (ref "SG4") (pin "-") (pinfunction "+_-") (pintype "passive"))
    )
    (net (code "60") (name "Net-(U$1-A)") (class "Default")
      (node (ref "R12") (pin "2") (pinfunction "2_2") (pintype "passive"))
      (node (ref "U$1") (pin "P$15") (pinfunction "A_P$15") (pintype "power_in"))
    )
    (net (code "61") (name "VIN") (class "Default")
      (node (ref "C12") (pin "2") (pinfunction "2_2") (pintype "passive"))
      (node (ref "C13") (pin "+") (pinfunction "+_+") (pintype "passive"))
      (node (ref "D1") (pin "C") (pinfunction "C_C") (pintype "passive"))
      (node (ref "D2") (pin "C") (pinfunction "C_C") (pintype "passive"))
      (node (ref "D3") (pin "C") (pinfunction "C_C") (pintype "passive"))
      (node (ref "HT") (pin "1") (pinfunction "KL_1") (pintype "passive"))
      (node (ref "IC4") (pin "3") (pinfunction "VI_3") (pintype "input"))
      (node (ref "POWER1") (pin "6") (pinfunction "6_6") (pintype "passive"))
      (node (ref "PUMP") (pin "1") (pinfunction "KL_1") (pintype "passive"))
      (node (ref "R21") (pin "2") (pinfunction "2_2") (pintype "passive"))
      (node (ref "SG4") (pin "+") (pinfunction "-_+") (pintype "passive"))
    )
    (net (code "62") (name "unconnected-(IC3-AVCC-NC-Pad24)") (class "Default")
      (node (ref "IC3") (pin "24") (pinfunction "AVCC-NC_24") (pintype "no_connect"))
    )
    (net (code "63") (name "unconnected-(IC3-GPIO2-Pad13)") (class "Default")
      (node (ref "IC3") (pin "13") (pinfunction "GPIO2_13") (pintype "output"))
    )
    (net (code "64") (name "unconnected-(IC3-GPIO3-Pad14)") (class "Default")
      (node (ref "IC3") (pin "14") (pinfunction "GPIO3_14") (pintype "input"))
    )
    (net (code "65") (name "unconnected-(IC3-OSCI-Pad27)") (class "Default")
      (node (ref "IC3") (pin "27") (pinfunction "OSCI_27") (pintype "input"))
    )
    (net (code "66") (name "unconnected-(IC3-OSCO-Pad28)") (class "Default")
      (node (ref "IC3") (pin "28") (pinfunction "OSCO_28") (pintype "output"))
    )
    (net (code "67") (name "unconnected-(IC3-SLEEP#-Pad12)") (class "Default")
      (node (ref "IC3") (pin "12") (pinfunction "SLEEP#_12") (pintype "input"))
    )
    (net (code "68") (name "unconnected-(IC3-VCC3I-NC-Pad8)") (class "Default")
      (node (ref "IC3") (pin "8") (pinfunction "VCC3I-NC_8") (pintype "no_connect"))
    )
    (net (code "69") (name "unconnected-(JP3-Pad5)") (class "Default")
      (node (ref "JP3") (pin "5") (pinfunction "5_5") (pintype "passive"))
    )
  )
)
